# Pots.net
KiCad netlist of a schematic drawn in EAGLE
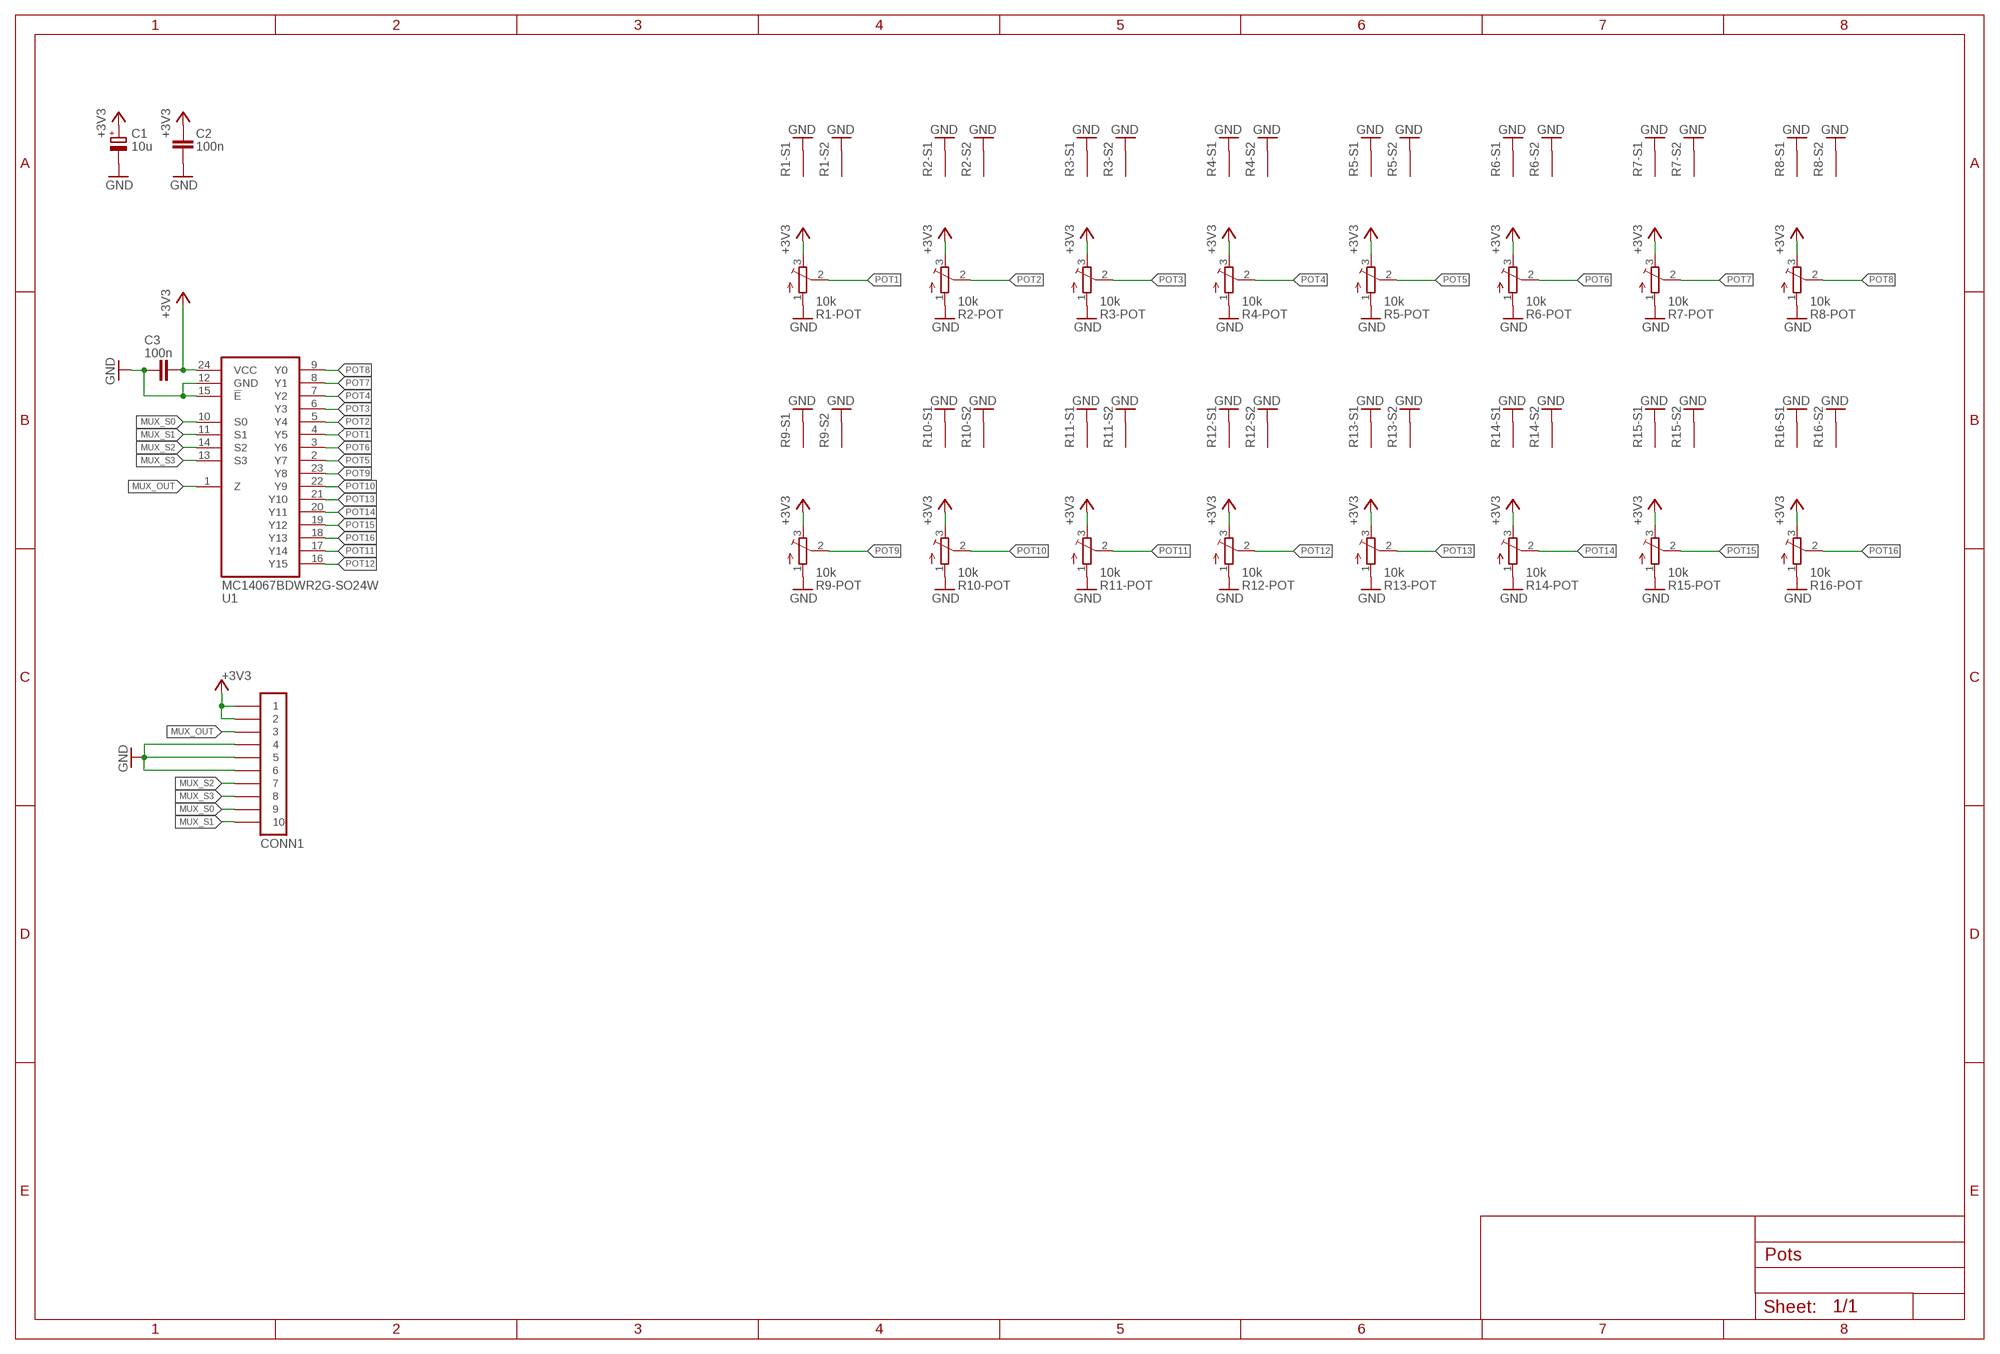
[diagram p0: schematic, sheet 1]

(export (version "E")
  (design (tool "Eeschema 10.0.6"))
  (components
    (comp (ref "C1")
      (value "10u")
      (footprint "eagle-import:153CLV-0405")
      (fields (field (name "MANUFACTURER") "Multicomp") (field (name "MPN") "MCVVT016M100CA1L"))
      (libsource (lib "eagle-import") (part "ELECTROLYTIC_CAPACITOR-CLV-040516V"))
    )
    (comp (ref "C2")
      (value "100n")
      (footprint "eagle-import:C0805")
      (libsource (lib "eagle-import") (part "CAPACITOR-0805"))
    )
    (comp (ref "C3")
      (value "100n")
      (footprint "eagle-import:C0805")
      (libsource (lib "eagle-import") (part "CAPACITOR-0805"))
    )
    (comp (ref "CONN1")
      (value "PINHD-1X10-FFC-1MM-Z")
      (footprint "eagle-import:MOLEX-52271-1079")
      (libsource (lib "eagle-import") (part "PINHD-1X10-FFC-1MM-Z"))
    )
    (comp (ref "R1")
      (value "10k")
      (footprint "eagle-import:PTV09A-4025F-B103")
      (libsource (lib "eagle-import") (part "PTV09A-4025F-B103"))
    )
    (comp (ref "R2")
      (value "10k")
      (footprint "eagle-import:PTV09A-4025F-B103")
      (libsource (lib "eagle-import") (part "PTV09A-4025F-B103"))
    )
    (comp (ref "R3")
      (value "10k")
      (footprint "eagle-import:PTV09A-4025F-B103")
      (libsource (lib "eagle-import") (part "PTV09A-4025F-B103"))
    )
    (comp (ref "R4")
      (value "10k")
      (footprint "eagle-import:PTV09A-4025F-B103")
      (libsource (lib "eagle-import") (part "PTV09A-4025F-B103"))
    )
    (comp (ref "R5")
      (value "10k")
      (footprint "eagle-import:PTV09A-4025F-B103")
      (libsource (lib "eagle-import") (part "PTV09A-4025F-B103"))
    )
    (comp (ref "R6")
      (value "10k")
      (footprint "eagle-import:PTV09A-4025F-B103")
      (libsource (lib "eagle-import") (part "PTV09A-4025F-B103"))
    )
    (comp (ref "R7")
      (value "10k")
      (footprint "eagle-import:PTV09A-4025F-B103")
      (libsource (lib "eagle-import") (part "PTV09A-4025F-B103"))
    )
    (comp (ref "R8")
      (value "10k")
      (footprint "eagle-import:PTV09A-4025F-B103")
      (libsource (lib "eagle-import") (part "PTV09A-4025F-B103"))
    )
    (comp (ref "R9")
      (value "10k")
      (footprint "eagle-import:PTV09A-4025F-B103")
      (libsource (lib "eagle-import") (part "PTV09A-4025F-B103"))
    )
    (comp (ref "R10")
      (value "10k")
      (footprint "eagle-import:PTV09A-4025F-B103")
      (libsource (lib "eagle-import") (part "PTV09A-4025F-B103"))
    )
    (comp (ref "R11")
      (value "10k")
      (footprint "eagle-import:PTV09A-4025F-B103")
      (libsource (lib "eagle-import") (part "PTV09A-4025F-B103"))
    )
    (comp (ref "R12")
      (value "10k")
      (footprint "eagle-import:PTV09A-4025F-B103")
      (libsource (lib "eagle-import") (part "PTV09A-4025F-B103"))
    )
    (comp (ref "R13")
      (value "10k")
      (footprint "eagle-import:PTV09A-4025F-B103")
      (libsource (lib "eagle-import") (part "PTV09A-4025F-B103"))
    )
    (comp (ref "R14")
      (value "10k")
      (footprint "eagle-import:PTV09A-4025F-B103")
      (libsource (lib "eagle-import") (part "PTV09A-4025F-B103"))
    )
    (comp (ref "R15")
      (value "10k")
      (footprint "eagle-import:PTV09A-4025F-B103")
      (libsource (lib "eagle-import") (part "PTV09A-4025F-B103"))
    )
    (comp (ref "R16")
      (value "10k")
      (footprint "eagle-import:PTV09A-4025F-B103")
      (libsource (lib "eagle-import") (part "PTV09A-4025F-B103"))
    )
    (comp (ref "U1")
      (value "MC14067BDWR2G-SO24W")
      (footprint "eagle-import:SO24-W")
      (fields (field (name "MANUFACTURER") "ON Semiconductor") (field (name "MPN") "MC14067BDWR2G"))
      (libsource (lib "eagle-import") (part "MC14067BDWR2G-SO24W"))
    )
  )
  (nets
    (net (code "1") (name "+3V3") (class "Default")
      (node (ref "C1") (pin "+") (pinfunction "+_+") (pintype "passive"))
      (node (ref "C2") (pin "1") (pinfunction "1_1") (pintype "passive"))
      (node (ref "C3") (pin "2") (pinfunction "2_2") (pintype "passive"))
      (node (ref "CONN1") (pin "1") (pinfunction "1_1") (pintype "passive"))
      (node (ref "CONN1") (pin "2") (pinfunction "2_2") (pintype "passive"))
      (node (ref "R1") (pin "3") (pinfunction "3_3") (pintype "passive"))
      (node (ref "R10") (pin "3") (pinfunction "3_3") (pintype "passive"))
      (node (ref "R11") (pin "3") (pinfunction "3_3") (pintype "passive"))
      (node (ref "R12") (pin "3") (pinfunction "3_3") (pintype "passive"))
      (node (ref "R13") (pin "3") (pinfunction "3_3") (pintype "passive"))
      (node (ref "R14") (pin "3") (pinfunction "3_3") (pintype "passive"))
      (node (ref "R15") (pin "3") (pinfunction "3_3") (pintype "passive"))
      (node (ref "R16") (pin "3") (pinfunction "3_3") (pintype "passive"))
      (node (ref "R2") (pin "3") (pinfunction "3_3") (pintype "passive"))
      (node (ref "R3") (pin "3") (pinfunction "3_3") (pintype "passive"))
      (node (ref "R4") (pin "3") (pinfunction "3_3") (pintype "passive"))
      (node (ref "R5") (pin "3") (pinfunction "3_3") (pintype "passive"))
      (node (ref "R6") (pin "3") (pinfunction "3_3") (pintype "passive"))
      (node (ref "R7") (pin "3") (pinfunction "3_3") (pintype "passive"))
      (node (ref "R8") (pin "3") (pinfunction "3_3") (pintype "passive"))
      (node (ref "R9") (pin "3") (pinfunction "3_3") (pintype "passive"))
      (node (ref "U1") (pin "24") (pinfunction "VCC_24") (pintype "passive"))
    )
    (net (code "2") (name "GND") (class "Default")
      (node (ref "C1") (pin "-") (pinfunction "-_-") (pintype "passive"))
      (node (ref "C2") (pin "2") (pinfunction "2_2") (pintype "passive"))
      (node (ref "C3") (pin "1") (pinfunction "1_1") (pintype "passive"))
      (node (ref "CONN1") (pin "4") (pinfunction "4_4") (pintype "passive"))
      (node (ref "CONN1") (pin "5") (pinfunction "5_5") (pintype "passive"))
      (node (ref "CONN1") (pin "6") (pinfunction "6_6") (pintype "passive"))
      (node (ref "R1") (pin "1") (pinfunction "1_1") (pintype "passive"))
      (node (ref "R1") (pin "S1") (pinfunction "S_S1") (pintype "passive"))
      (node (ref "R1") (pin "S2") (pinfunction "S_S2") (pintype "passive"))
      (node (ref "R10") (pin "1") (pinfunction "1_1") (pintype "passive"))
      (node (ref "R10") (pin "S1") (pinfunction "S_S1") (pintype "passive"))
      (node (ref "R10") (pin "S2") (pinfunction "S_S2") (pintype "passive"))
      (node (ref "R11") (pin "1") (pinfunction "1_1") (pintype "passive"))
      (node (ref "R11") (pin "S1") (pinfunction "S_S1") (pintype "passive"))
      (node (ref "R11") (pin "S2") (pinfunction "S_S2") (pintype "passive"))
      (node (ref "R12") (pin "1") (pinfunction "1_1") (pintype "passive"))
      (node (ref "R12") (pin "S1") (pinfunction "S_S1") (pintype "passive"))
      (node (ref "R12") (pin "S2") (pinfunction "S_S2") (pintype "passive"))
      (node (ref "R13") (pin "1") (pinfunction "1_1") (pintype "passive"))
      (node (ref "R13") (pin "S1") (pinfunction "S_S1") (pintype "passive"))
      (node (ref "R13") (pin "S2") (pinfunction "S_S2") (pintype "passive"))
      (node (ref "R14") (pin "1") (pinfunction "1_1") (pintype "passive"))
      (node (ref "R14") (pin "S1") (pinfunction "S_S1") (pintype "passive"))
      (node (ref "R14") (pin "S2") (pinfunction "S_S2") (pintype "passive"))
      (node (ref "R15") (pin "1") (pinfunction "1_1") (pintype "passive"))
      (node (ref "R15") (pin "S1") (pinfunction "S_S1") (pintype "passive"))
      (node (ref "R15") (pin "S2") (pinfunction "S_S2") (pintype "passive"))
      (node (ref "R16") (pin "1") (pinfunction "1_1") (pintype "passive"))
      (node (ref "R16") (pin "S1") (pinfunction "S_S1") (pintype "passive"))
      (node (ref "R16") (pin "S2") (pinfunction "S_S2") (pintype "passive"))
      (node (ref "R2") (pin "1") (pinfunction "1_1") (pintype "passive"))
      (node (ref "R2") (pin "S1") (pinfunction "S_S1") (pintype "passive"))
      (node (ref "R2") (pin "S2") (pinfunction "S_S2") (pintype "passive"))
      (node (ref "R3") (pin "1") (pinfunction "1_1") (pintype "passive"))
      (node (ref "R3") (pin "S1") (pinfunction "S_S1") (pintype "passive"))
      (node (ref "R3") (pin "S2") (pinfunction "S_S2") (pintype "passive"))
      (node (ref "R4") (pin "1") (pinfunction "1_1") (pintype "passive"))
      (node (ref "R4") (pin "S1") (pinfunction "S_S1") (pintype "passive"))
      (node (ref "R4") (pin "S2") (pinfunction "S_S2") (pintype "passive"))
      (node (ref "R5") (pin "1") (pinfunction "1_1") (pintype "passive"))
      (node (ref "R5") (pin "S1") (pinfunction "S_S1") (pintype "passive"))
      (node (ref "R5") (pin "S2") (pinfunction "S_S2") (pintype "passive"))
      (node (ref "R6") (pin "1") (pinfunction "1_1") (pintype "passive"))
      (node (ref "R6") (pin "S1") (pinfunction "S_S1") (pintype "passive"))
      (node (ref "R6") (pin "S2") (pinfunction "S_S2") (pintype "passive"))
      (node (ref "R7") (pin "1") (pinfunction "1_1") (pintype "passive"))
      (node (ref "R7") (pin "S1") (pinfunction "S_S1") (pintype "passive"))
      (node (ref "R7") (pin "S2") (pinfunction "S_S2") (pintype "passive"))
      (node (ref "R8") (pin "1") (pinfunction "1_1") (pintype "passive"))
      (node (ref "R8") (pin "S1") (pinfunction "S_S1") (pintype "passive"))
      (node (ref "R8") (pin "S2") (pinfunction "S_S2") (pintype "passive"))
      (node (ref "R9") (pin "1") (pinfunction "1_1") (pintype "passive"))
      (node (ref "R9") (pin "S1") (pinfunction "S_S1") (pintype "passive"))
      (node (ref "R9") (pin "S2") (pinfunction "S_S2") (pintype "passive"))
      (node (ref "U1") (pin "12") (pinfunction "GND_12") (pintype "passive"))
      (node (ref "U1") (pin "15") (pinfunction "~{E}_15") (pintype "input"))
    )
    (net (code "3") (name "MUX_OUT") (class "Default")
      (node (ref "CONN1") (pin "3") (pinfunction "3_3") (pintype "passive"))
      (node (ref "U1") (pin "1") (pinfunction "Z_1") (pintype "bidirectional"))
    )
    (net (code "4") (name "MUX_S0") (class "Default")
      (node (ref "CONN1") (pin "9") (pinfunction "9_9") (pintype "passive"))
      (node (ref "U1") (pin "10") (pinfunction "S0_10") (pintype "input"))
    )
    (net (code "5") (name "MUX_S1") (class "Default")
      (node (ref "CONN1") (pin "10") (pinfunction "10_10") (pintype "passive"))
      (node (ref "U1") (pin "11") (pinfunction "S1_11") (pintype "input"))
    )
    (net (code "6") (name "MUX_S2") (class "Default")
      (node (ref "CONN1") (pin "7") (pinfunction "7_7") (pintype "passive"))
      (node (ref "U1") (pin "14") (pinfunction "S2_14") (pintype "input"))
    )
    (net (code "7") (name "MUX_S3") (class "Default")
      (node (ref "CONN1") (pin "8") (pinfunction "8_8") (pintype "passive"))
      (node (ref "U1") (pin "13") (pinfunction "S3_13") (pintype "input"))
    )
    (net (code "8") (name "POT1") (class "Default")
      (node (ref "R1") (pin "2") (pinfunction "2_2") (pintype "passive"))
      (node (ref "U1") (pin "4") (pinfunction "Y5_4") (pintype "bidirectional"))
    )
    (net (code "9") (name "POT2") (class "Default")
      (node (ref "R2") (pin "2") (pinfunction "2_2") (pintype "passive"))
      (node (ref "U1") (pin "5") (pinfunction "Y4_5") (pintype "bidirectional"))
    )
    (net (code "10") (name "POT3") (class "Default")
      (node (ref "R3") (pin "2") (pinfunction "2_2") (pintype "passive"))
      (node (ref "U1") (pin "6") (pinfunction "Y3_6") (pintype "bidirectional"))
    )
    (net (code "11") (name "POT4") (class "Default")
      (node (ref "R4") (pin "2") (pinfunction "2_2") (pintype "passive"))
      (node (ref "U1") (pin "7") (pinfunction "Y2_7") (pintype "bidirectional"))
    )
    (net (code "12") (name "POT5") (class "Default")
      (node (ref "R5") (pin "2") (pinfunction "2_2") (pintype "passive"))
      (node (ref "U1") (pin "2") (pinfunction "Y7_2") (pintype "bidirectional"))
    )
    (net (code "13") (name "POT6") (class "Default")
      (node (ref "R6") (pin "2") (pinfunction "2_2") (pintype "passive"))
      (node (ref "U1") (pin "3") (pinfunction "Y6_3") (pintype "bidirectional"))
    )
    (net (code "14") (name "POT7") (class "Default")
      (node (ref "R7") (pin "2") (pinfunction "2_2") (pintype "passive"))
      (node (ref "U1") (pin "8") (pinfunction "Y1_8") (pintype "bidirectional"))
    )
    (net (code "15") (name "POT8") (class "Default")
      (node (ref "R8") (pin "2") (pinfunction "2_2") (pintype "passive"))
      (node (ref "U1") (pin "9") (pinfunction "Y0_9") (pintype "bidirectional"))
    )
    (net (code "16") (name "POT9") (class "Default")
      (node (ref "R9") (pin "2") (pinfunction "2_2") (pintype "passive"))
      (node (ref "U1") (pin "23") (pinfunction "Y8_23") (pintype "bidirectional"))
    )
    (net (code "17") (name "POT10") (class "Default")
      (node (ref "R10") (pin "2") (pinfunction "2_2") (pintype "passive"))
      (node (ref "U1") (pin "22") (pinfunction "Y9_22") (pintype "bidirectional"))
    )
    (net (code "18") (name "POT11") (class "Default")
      (node (ref "R11") (pin "2") (pinfunction "2_2") (pintype "passive"))
      (node (ref "U1") (pin "17") (pinfunction "Y14_17") (pintype "bidirectional"))
    )
    (net (code "19") (name "POT12") (class "Default")
      (node (ref "R12") (pin "2") (pinfunction "2_2") (pintype "passive"))
      (node (ref "U1") (pin "16") (pinfunction "Y15_16") (pintype "bidirectional"))
    )
    (net (code "20") (name "POT13") (class "Default")
      (node (ref "R13") (pin "2") (pinfunction "2_2") (pintype "passive"))
      (node (ref "U1") (pin "21") (pinfunction "Y10_21") (pintype "bidirectional"))
    )
    (net (code "21") (name "POT14") (class "Default")
      (node (ref "R14") (pin "2") (pinfunction "2_2") (pintype "passive"))
      (node (ref "U1") (pin "20") (pinfunction "Y11_20") (pintype "bidirectional"))
    )
    (net (code "22") (name "POT15") (class "Default")
      (node (ref "R15") (pin "2") (pinfunction "2_2") (pintype "passive"))
      (node (ref "U1") (pin "19") (pinfunction "Y12_19") (pintype "bidirectional"))
    )
    (net (code "23") (name "POT16") (class "Default")
      (node (ref "R16") (pin "2") (pinfunction "2_2") (pintype "passive"))
      (node (ref "U1") (pin "18") (pinfunction "Y13_18") (pintype "bidirectional"))
    )
  )
)
